# 03-SNESDRONE_Direct_IO_LEVEL_SHIFTER_0.net
KiCad netlist of a schematic drawn in Altium Designer
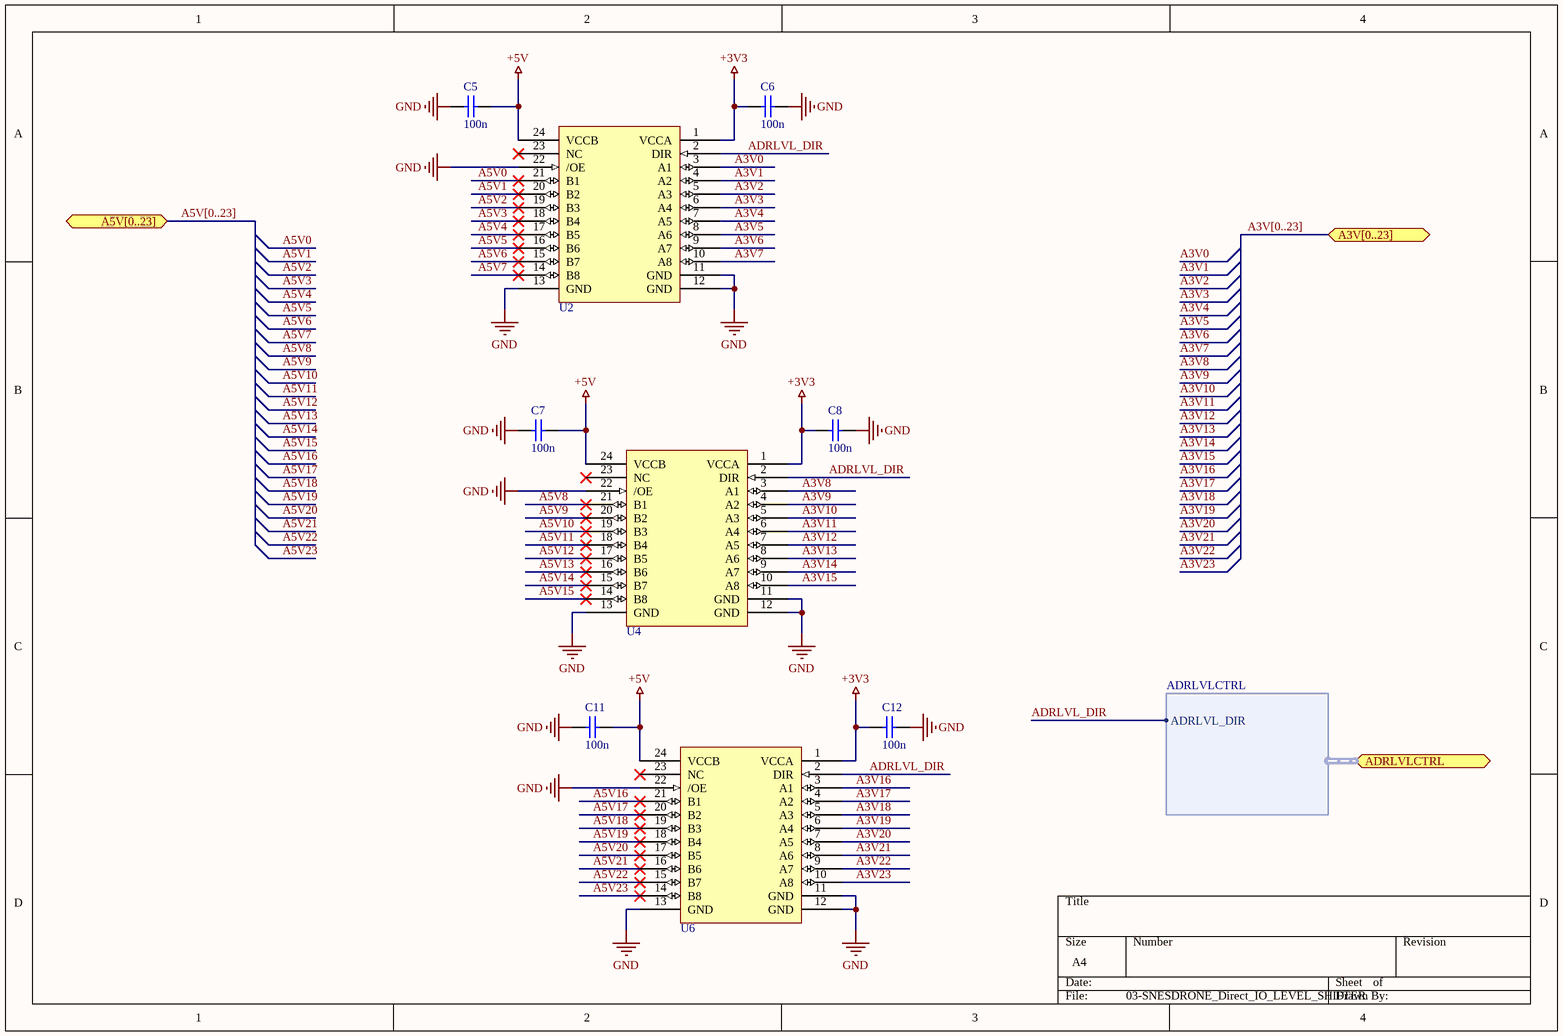
[diagram p0: 03-SNESDRONE_Direct_IO_LEVEL_SHIFTER_0.SchDoc]

(export (version "E")
  (design (tool "Eeschema 10.0.6"))
  (components
    (comp (ref "C5")
      (value "100n")
      (footprint "cap_0603")
      (description "Capacitor")
      (fields (field (name "Comment") "cap_0603"))
      (libsource (lib "mycomponents") (part "cap_0603"))
    )
    (comp (ref "C6")
      (value "100n")
      (footprint "cap_0603")
      (description "Capacitor")
      (fields (field (name "Comment") "cap_0603"))
      (libsource (lib "mycomponents") (part "cap_0603"))
    )
    (comp (ref "C7")
      (value "100n")
      (footprint "cap_0603")
      (description "Capacitor")
      (fields (field (name "Comment") "cap_0603"))
      (libsource (lib "mycomponents") (part "cap_0603"))
    )
    (comp (ref "C8")
      (value "100n")
      (footprint "cap_0603")
      (description "Capacitor")
      (fields (field (name "Comment") "cap_0603"))
      (libsource (lib "mycomponents") (part "cap_0603"))
    )
    (comp (ref "C11")
      (value "100n")
      (footprint "cap_0603")
      (description "Capacitor")
      (fields (field (name "Comment") "cap_0603"))
      (libsource (lib "mycomponents") (part "cap_0603"))
    )
    (comp (ref "C12")
      (value "100n")
      (footprint "cap_0603")
      (description "Capacitor")
      (fields (field (name "Comment") "cap_0603"))
      (libsource (lib "mycomponents") (part "cap_0603"))
    )
    (comp (ref "U2")
      (value "IC_SN74LVCC3245APWR")
      (footprint "TSSOP24")
      (description "Bus-Transceiver, Produktreihe LVC, 8 Eingänge, 50mA, 7ns, 2.3V bis 5.5V, TSSOP 24")
      (libsource (lib "mycomponents") (part "IC_SN74LVCC3245APWR"))
    )
    (comp (ref "U4")
      (value "IC_SN74LVCC3245APWR")
      (footprint "TSSOP24")
      (description "Bus-Transceiver, Produktreihe LVC, 8 Eingänge, 50mA, 7ns, 2.3V bis 5.5V, TSSOP 24")
      (libsource (lib "mycomponents") (part "IC_SN74LVCC3245APWR"))
    )
    (comp (ref "U6")
      (value "IC_SN74LVCC3245APWR")
      (footprint "TSSOP24")
      (description "Bus-Transceiver, Produktreihe LVC, 8 Eingänge, 50mA, 7ns, 2.3V bis 5.5V, TSSOP 24")
      (libsource (lib "mycomponents") (part "IC_SN74LVCC3245APWR"))
    )
  )
  (nets
    (net (code "2") (name "+3V3") (class "Default")
      (node (ref "C12") (pin "2") (pinfunction "2_2") (pintype "passive"))
      (node (ref "C6") (pin "2") (pinfunction "2_2") (pintype "passive"))
      (node (ref "C8") (pin "2") (pinfunction "2_2") (pintype "passive"))
      (node (ref "U2") (pin "1") (pinfunction "VCCA_1") (pintype "power_in"))
      (node (ref "U4") (pin "1") (pinfunction "VCCA_1") (pintype "power_in"))
      (node (ref "U6") (pin "1") (pinfunction "VCCA_1") (pintype "power_in"))
    )
    (net (code "3") (name "+5V") (class "Default")
      (node (ref "C11") (pin "1") (pinfunction "1_1") (pintype "passive"))
      (node (ref "C5") (pin "1") (pinfunction "1_1") (pintype "passive"))
      (node (ref "C7") (pin "1") (pinfunction "1_1") (pintype "passive"))
      (node (ref "U2") (pin "24") (pinfunction "VCCB_24") (pintype "power_in"))
      (node (ref "U4") (pin "24") (pinfunction "VCCB_24") (pintype "power_in"))
      (node (ref "U6") (pin "24") (pinfunction "VCCB_24") (pintype "power_in"))
    )
    (net (code "4") (name "/A3V0") (class "Default")
      (node (ref "U2") (pin "3") (pinfunction "A1_3") (pintype "bidirectional"))
    )
    (net (code "5") (name "/A3V1") (class "Default")
      (node (ref "U2") (pin "4") (pinfunction "A2_4") (pintype "bidirectional"))
    )
    (net (code "6") (name "/A3V2") (class "Default")
      (node (ref "U2") (pin "5") (pinfunction "A3_5") (pintype "bidirectional"))
    )
    (net (code "7") (name "/A3V3") (class "Default")
      (node (ref "U2") (pin "6") (pinfunction "A4_6") (pintype "bidirectional"))
    )
    (net (code "8") (name "/A3V4") (class "Default")
      (node (ref "U2") (pin "7") (pinfunction "A5_7") (pintype "bidirectional"))
    )
    (net (code "9") (name "/A3V5") (class "Default")
      (node (ref "U2") (pin "8") (pinfunction "A6_8") (pintype "bidirectional"))
    )
    (net (code "10") (name "/A3V6") (class "Default")
      (node (ref "U2") (pin "9") (pinfunction "A7_9") (pintype "bidirectional"))
    )
    (net (code "11") (name "/A3V7") (class "Default")
      (node (ref "U2") (pin "10") (pinfunction "A8_10") (pintype "bidirectional"))
    )
    (net (code "12") (name "/A3V8") (class "Default")
      (node (ref "U4") (pin "3") (pinfunction "A1_3") (pintype "bidirectional"))
    )
    (net (code "13") (name "/A3V9") (class "Default")
      (node (ref "U4") (pin "4") (pinfunction "A2_4") (pintype "bidirectional"))
    )
    (net (code "14") (name "/A3V10") (class "Default")
      (node (ref "U4") (pin "5") (pinfunction "A3_5") (pintype "bidirectional"))
    )
    (net (code "15") (name "/A3V11") (class "Default")
      (node (ref "U4") (pin "6") (pinfunction "A4_6") (pintype "bidirectional"))
    )
    (net (code "16") (name "/A3V12") (class "Default")
      (node (ref "U4") (pin "7") (pinfunction "A5_7") (pintype "bidirectional"))
    )
    (net (code "17") (name "/A3V13") (class "Default")
      (node (ref "U4") (pin "8") (pinfunction "A6_8") (pintype "bidirectional"))
    )
    (net (code "18") (name "/A3V14") (class "Default")
      (node (ref "U4") (pin "9") (pinfunction "A7_9") (pintype "bidirectional"))
    )
    (net (code "19") (name "/A3V15") (class "Default")
      (node (ref "U4") (pin "10") (pinfunction "A8_10") (pintype "bidirectional"))
    )
    (net (code "20") (name "/A3V16") (class "Default")
      (node (ref "U6") (pin "3") (pinfunction "A1_3") (pintype "bidirectional"))
    )
    (net (code "21") (name "/A3V17") (class "Default")
      (node (ref "U6") (pin "4") (pinfunction "A2_4") (pintype "bidirectional"))
    )
    (net (code "22") (name "/A3V18") (class "Default")
      (node (ref "U6") (pin "5") (pinfunction "A3_5") (pintype "bidirectional"))
    )
    (net (code "23") (name "/A3V19") (class "Default")
      (node (ref "U6") (pin "6") (pinfunction "A4_6") (pintype "bidirectional"))
    )
    (net (code "24") (name "/A3V20") (class "Default")
      (node (ref "U6") (pin "7") (pinfunction "A5_7") (pintype "bidirectional"))
    )
    (net (code "25") (name "/A3V21") (class "Default")
      (node (ref "U6") (pin "8") (pinfunction "A6_8") (pintype "bidirectional"))
    )
    (net (code "26") (name "/A3V22") (class "Default")
      (node (ref "U6") (pin "9") (pinfunction "A7_9") (pintype "bidirectional"))
    )
    (net (code "27") (name "/A3V23") (class "Default")
      (node (ref "U6") (pin "10") (pinfunction "A8_10") (pintype "bidirectional"))
    )
    (net (code "29") (name "/A5V0") (class "Default")
      (node (ref "U2") (pin "21") (pinfunction "B1_21") (pintype "bidirectional"))
    )
    (net (code "30") (name "/A5V1") (class "Default")
      (node (ref "U2") (pin "20") (pinfunction "B2_20") (pintype "bidirectional"))
    )
    (net (code "31") (name "/A5V2") (class "Default")
      (node (ref "U2") (pin "19") (pinfunction "B3_19") (pintype "bidirectional"))
    )
    (net (code "32") (name "/A5V3") (class "Default")
      (node (ref "U2") (pin "18") (pinfunction "B4_18") (pintype "bidirectional"))
    )
    (net (code "33") (name "/A5V4") (class "Default")
      (node (ref "U2") (pin "17") (pinfunction "B5_17") (pintype "bidirectional+no_connect"))
    )
    (net (code "34") (name "/A5V5") (class "Default")
      (node (ref "U2") (pin "16") (pinfunction "B6_16") (pintype "bidirectional+no_connect"))
    )
    (net (code "35") (name "/A5V6") (class "Default")
      (node (ref "U2") (pin "15") (pinfunction "B7_15") (pintype "bidirectional+no_connect"))
    )
    (net (code "36") (name "/A5V7") (class "Default")
      (node (ref "U2") (pin "14") (pinfunction "B8_14") (pintype "bidirectional+no_connect"))
    )
    (net (code "37") (name "/A5V8") (class "Default")
      (node (ref "U4") (pin "21") (pinfunction "B1_21") (pintype "bidirectional+no_connect"))
    )
    (net (code "38") (name "/A5V9") (class "Default")
      (node (ref "U4") (pin "20") (pinfunction "B2_20") (pintype "bidirectional+no_connect"))
    )
    (net (code "39") (name "/A5V10") (class "Default")
      (node (ref "U4") (pin "19") (pinfunction "B3_19") (pintype "bidirectional+no_connect"))
    )
    (net (code "40") (name "/A5V11") (class "Default")
      (node (ref "U4") (pin "18") (pinfunction "B4_18") (pintype "bidirectional+no_connect"))
    )
    (net (code "41") (name "/A5V12") (class "Default")
      (node (ref "U4") (pin "17") (pinfunction "B5_17") (pintype "bidirectional+no_connect"))
    )
    (net (code "42") (name "/A5V13") (class "Default")
      (node (ref "U4") (pin "16") (pinfunction "B6_16") (pintype "bidirectional+no_connect"))
    )
    (net (code "43") (name "/A5V14") (class "Default")
      (node (ref "U4") (pin "15") (pinfunction "B7_15") (pintype "bidirectional+no_connect"))
    )
    (net (code "44") (name "/A5V15") (class "Default")
      (node (ref "U4") (pin "14") (pinfunction "B8_14") (pintype "bidirectional+no_connect"))
    )
    (net (code "45") (name "/A5V16") (class "Default")
      (node (ref "U6") (pin "21") (pinfunction "B1_21") (pintype "bidirectional+no_connect"))
    )
    (net (code "46") (name "/A5V17") (class "Default")
      (node (ref "U6") (pin "20") (pinfunction "B2_20") (pintype "bidirectional+no_connect"))
    )
    (net (code "47") (name "/A5V18") (class "Default")
      (node (ref "U6") (pin "19") (pinfunction "B3_19") (pintype "bidirectional+no_connect"))
    )
    (net (code "48") (name "/A5V19") (class "Default")
      (node (ref "U6") (pin "18") (pinfunction "B4_18") (pintype "bidirectional+no_connect"))
    )
    (net (code "49") (name "/A5V20") (class "Default")
      (node (ref "U6") (pin "17") (pinfunction "B5_17") (pintype "bidirectional+no_connect"))
    )
    (net (code "50") (name "/A5V21") (class "Default")
      (node (ref "U6") (pin "16") (pinfunction "B6_16") (pintype "bidirectional+no_connect"))
    )
    (net (code "51") (name "/A5V22") (class "Default")
      (node (ref "U6") (pin "15") (pinfunction "B7_15") (pintype "bidirectional+no_connect"))
    )
    (net (code "52") (name "/A5V23") (class "Default")
      (node (ref "U6") (pin "14") (pinfunction "B8_14") (pintype "bidirectional+no_connect"))
    )
    (net (code "54") (name "/ADRLVL_DIR") (class "Default")
      (node (ref "U2") (pin "2") (pinfunction "DIR_2") (pintype "input"))
      (node (ref "U4") (pin "2") (pinfunction "DIR_2") (pintype "input"))
      (node (ref "U6") (pin "2") (pinfunction "DIR_2") (pintype "input"))
    )
    (net (code "56") (name "GND") (class "Default")
      (node (ref "C11") (pin "2") (pinfunction "2_2") (pintype "passive"))
      (node (ref "C12") (pin "1") (pinfunction "1_1") (pintype "passive"))
      (node (ref "C5") (pin "2") (pinfunction "2_2") (pintype "passive"))
      (node (ref "C6") (pin "1") (pinfunction "1_1") (pintype "passive"))
      (node (ref "C7") (pin "2") (pinfunction "2_2") (pintype "passive"))
      (node (ref "C8") (pin "1") (pinfunction "1_1") (pintype "passive"))
      (node (ref "U2") (pin "11") (pinfunction "GND_11") (pintype "power_in"))
      (node (ref "U2") (pin "12") (pinfunction "GND_12") (pintype "power_in"))
      (node (ref "U2") (pin "13") (pinfunction "GND_13") (pintype "power_in"))
      (node (ref "U2") (pin "22") (pinfunction "/OE_22") (pintype "input"))
      (node (ref "U4") (pin "11") (pinfunction "GND_11") (pintype "power_in"))
      (node (ref "U4") (pin "12") (pinfunction "GND_12") (pintype "power_in"))
      (node (ref "U4") (pin "13") (pinfunction "GND_13") (pintype "power_in"))
      (node (ref "U4") (pin "22") (pinfunction "/OE_22") (pintype "input"))
      (node (ref "U6") (pin "11") (pinfunction "GND_11") (pintype "power_in"))
      (node (ref "U6") (pin "12") (pinfunction "GND_12") (pintype "power_in"))
      (node (ref "U6") (pin "13") (pinfunction "GND_13") (pintype "power_in"))
      (node (ref "U6") (pin "22") (pinfunction "/OE_22") (pintype "input"))
    )
    (net (code "57") (name "unconnected-(U2-NC-Pad23)") (class "Default")
      (node (ref "U2") (pin "23") (pinfunction "NC_23") (pintype "passive+no_connect"))
    )
    (net (code "58") (name "unconnected-(U4-NC-Pad23)") (class "Default")
      (node (ref "U4") (pin "23") (pinfunction "NC_23") (pintype "passive+no_connect"))
    )
    (net (code "59") (name "unconnected-(U6-NC-Pad23)") (class "Default")
      (node (ref "U6") (pin "23") (pinfunction "NC_23") (pintype "passive+no_connect"))
    )
  )
)
